# PicoCradle.net
KiCad netlist of a schematic drawn in EAGLE
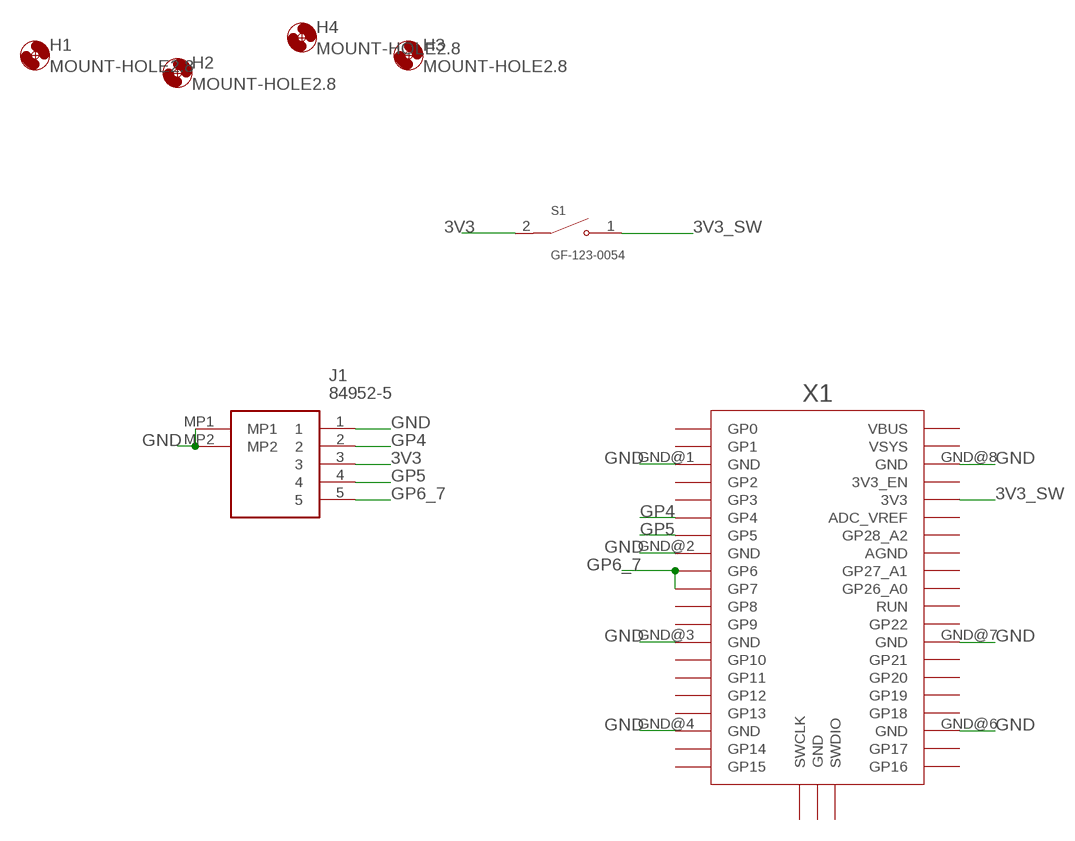
[diagram p0: schematic, sheet 1]

(export (version "E")
  (design (tool "Eeschema 10.0.6"))
  (components
    (comp (ref "H1")
      (value "MOUNT-HOLE2.8")
      (footprint "eagle-import:2,8")
      (libsource (lib "eagle-import") (part "MOUNT-HOLE2.8"))
    )
    (comp (ref "H2")
      (value "MOUNT-HOLE2.8")
      (footprint "eagle-import:2,8")
      (libsource (lib "eagle-import") (part "MOUNT-HOLE2.8"))
    )
    (comp (ref "H3")
      (value "MOUNT-HOLE2.8")
      (footprint "eagle-import:2,8")
      (libsource (lib "eagle-import") (part "MOUNT-HOLE2.8"))
    )
    (comp (ref "H4")
      (value "MOUNT-HOLE2.8")
      (footprint "eagle-import:2,8")
      (libsource (lib "eagle-import") (part "MOUNT-HOLE2.8"))
    )
    (comp (ref "J1")
      (value "84952-5")
      (footprint "eagle-import:849525")
      (libsource (lib "eagle-import") (part "84952-5"))
    )
    (comp (ref "S1")
      (value "GF-123-0054")
      (footprint "eagle-import:SW_GF-123-0054")
      (fields (field (name "MF") "CW Industries"))
      (libsource (lib "eagle-import") (part "GF-123-0054"))
    )
    (comp (ref "X1")
      (value "RPI_PICO_IG-SMD")
      (footprint "eagle-import:RPI_PICO")
      (libsource (lib "eagle-import") (part "RPI_PICO_IG-SMD"))
    )
  )
  (nets
    (net (code "1") (name "/3V3") (class "Default")
      (node (ref "J1") (pin "3") (pinfunction "3_3") (pintype "bidirectional"))
      (node (ref "S1") (pin "2") (pinfunction "2_2") (pintype "passive"))
    )
    (net (code "2") (name "/3V3_SW") (class "Default")
      (node (ref "S1") (pin "1") (pinfunction "1_1") (pintype "passive"))
      (node (ref "X1") (pin "3V3") (pinfunction "3V3_3V3") (pintype "bidirectional"))
    )
    (net (code "3") (name "/GND") (class "Default")
      (node (ref "J1") (pin "1") (pinfunction "1_1") (pintype "bidirectional"))
      (node (ref "J1") (pin "MP1") (pinfunction "MP1_MP1") (pintype "bidirectional"))
      (node (ref "J1") (pin "MP2") (pinfunction "MP2_MP2") (pintype "bidirectional"))
      (node (ref "X1") (pin "GND@1") (pinfunction "GND_GND@1") (pintype "bidirectional"))
      (node (ref "X1") (pin "GND@2") (pinfunction "GND_GND@2") (pintype "bidirectional"))
      (node (ref "X1") (pin "GND@3") (pinfunction "GND_GND@3") (pintype "bidirectional"))
      (node (ref "X1") (pin "GND@4") (pinfunction "GND_GND@4") (pintype "bidirectional"))
      (node (ref "X1") (pin "GND@6") (pinfunction "GND_GND@6") (pintype "bidirectional"))
      (node (ref "X1") (pin "GND@7") (pinfunction "GND_GND@7") (pintype "bidirectional"))
      (node (ref "X1") (pin "GND@8") (pinfunction "GND_GND@8") (pintype "bidirectional"))
    )
    (net (code "4") (name "/GP4") (class "Default")
      (node (ref "J1") (pin "2") (pinfunction "2_2") (pintype "bidirectional"))
      (node (ref "X1") (pin "GP4") (pinfunction "GP4_GP4") (pintype "bidirectional"))
    )
    (net (code "5") (name "/GP5") (class "Default")
      (node (ref "J1") (pin "4") (pinfunction "4_4") (pintype "bidirectional"))
      (node (ref "X1") (pin "GP5") (pinfunction "GP5_GP5") (pintype "bidirectional"))
    )
    (net (code "6") (name "/GP6_7") (class "Default")
      (node (ref "J1") (pin "5") (pinfunction "5_5") (pintype "bidirectional"))
      (node (ref "X1") (pin "GP6") (pinfunction "GP6_GP6") (pintype "bidirectional"))
      (node (ref "X1") (pin "GP7") (pinfunction "GP7_GP7") (pintype "bidirectional"))
    )
    (net (code "7") (name "unconnected-(X1-GND-PadGND@5)") (class "Default")
      (node (ref "X1") (pin "GND@5") (pinfunction "GND_GND@5") (pintype "bidirectional"))
    )
    (net (code "8") (name "unconnected-(X1-Pad3V3_EN)") (class "Default")
      (node (ref "X1") (pin "3V3_EN") (pinfunction "3V3_EN_3V3_EN") (pintype "bidirectional"))
    )
    (net (code "9") (name "unconnected-(X1-PadADC_VREF)") (class "Default")
      (node (ref "X1") (pin "ADC_VREF") (pinfunction "ADC_VREF_ADC_VREF") (pintype "bidirectional"))
    )
    (net (code "10") (name "unconnected-(X1-PadAGND)") (class "Default")
      (node (ref "X1") (pin "AGND") (pinfunction "AGND_AGND") (pintype "bidirectional"))
    )
    (net (code "11") (name "unconnected-(X1-PadGP0)") (class "Default")
      (node (ref "X1") (pin "GP0") (pinfunction "GP0_GP0") (pintype "bidirectional"))
    )
    (net (code "12") (name "unconnected-(X1-PadGP1)") (class "Default")
      (node (ref "X1") (pin "GP1") (pinfunction "GP1_GP1") (pintype "bidirectional"))
    )
    (net (code "13") (name "unconnected-(X1-PadGP2)") (class "Default")
      (node (ref "X1") (pin "GP2") (pinfunction "GP2_GP2") (pintype "bidirectional"))
    )
    (net (code "14") (name "unconnected-(X1-PadGP3)") (class "Default")
      (node (ref "X1") (pin "GP3") (pinfunction "GP3_GP3") (pintype "bidirectional"))
    )
    (net (code "15") (name "unconnected-(X1-PadGP8)") (class "Default")
      (node (ref "X1") (pin "GP8") (pinfunction "GP8_GP8") (pintype "bidirectional"))
    )
    (net (code "16") (name "unconnected-(X1-PadGP9)") (class "Default")
      (node (ref "X1") (pin "GP9") (pinfunction "GP9_GP9") (pintype "bidirectional"))
    )
    (net (code "17") (name "unconnected-(X1-PadGP10)") (class "Default")
      (node (ref "X1") (pin "GP10") (pinfunction "GP10_GP10") (pintype "bidirectional"))
    )
    (net (code "18") (name "unconnected-(X1-PadGP11)") (class "Default")
      (node (ref "X1") (pin "GP11") (pinfunction "GP11_GP11") (pintype "bidirectional"))
    )
    (net (code "19") (name "unconnected-(X1-PadGP12)") (class "Default")
      (node (ref "X1") (pin "GP12") (pinfunction "GP12_GP12") (pintype "bidirectional"))
    )
    (net (code "20") (name "unconnected-(X1-PadGP13)") (class "Default")
      (node (ref "X1") (pin "GP13") (pinfunction "GP13_GP13") (pintype "bidirectional"))
    )
    (net (code "21") (name "unconnected-(X1-PadGP14)") (class "Default")
      (node (ref "X1") (pin "GP14") (pinfunction "GP14_GP14") (pintype "bidirectional"))
    )
    (net (code "22") (name "unconnected-(X1-PadGP15)") (class "Default")
      (node (ref "X1") (pin "GP15") (pinfunction "GP15_GP15") (pintype "bidirectional"))
    )
    (net (code "23") (name "unconnected-(X1-PadGP16)") (class "Default")
      (node (ref "X1") (pin "GP16") (pinfunction "GP16_GP16") (pintype "bidirectional"))
    )
    (net (code "24") (name "unconnected-(X1-PadGP17)") (class "Default")
      (node (ref "X1") (pin "GP17") (pinfunction "GP17_GP17") (pintype "bidirectional"))
    )
    (net (code "25") (name "unconnected-(X1-PadGP18)") (class "Default")
      (node (ref "X1") (pin "GP18") (pinfunction "GP18_GP18") (pintype "bidirectional"))
    )
    (net (code "26") (name "unconnected-(X1-PadGP19)") (class "Default")
      (node (ref "X1") (pin "GP19") (pinfunction "GP19_GP19") (pintype "bidirectional"))
    )
    (net (code "27") (name "unconnected-(X1-PadGP20)") (class "Default")
      (node (ref "X1") (pin "GP20") (pinfunction "GP20_GP20") (pintype "bidirectional"))
    )
    (net (code "28") (name "unconnected-(X1-PadGP21)") (class "Default")
      (node (ref "X1") (pin "GP21") (pinfunction "GP21_GP21") (pintype "bidirectional"))
    )
    (net (code "29") (name "unconnected-(X1-PadGP22)") (class "Default")
      (node (ref "X1") (pin "GP22") (pinfunction "GP22_GP22") (pintype "bidirectional"))
    )
    (net (code "30") (name "unconnected-(X1-PadGP26_A0)") (class "Default")
      (node (ref "X1") (pin "GP26_A0") (pinfunction "GP26_A0_GP26_A0") (pintype "bidirectional"))
    )
    (net (code "31") (name "unconnected-(X1-PadGP27_A1)") (class "Default")
      (node (ref "X1") (pin "GP27_A1") (pinfunction "GP27_A1_GP27_A1") (pintype "bidirectional"))
    )
    (net (code "32") (name "unconnected-(X1-PadGP28_A2)") (class "Default")
      (node (ref "X1") (pin "GP28_A2") (pinfunction "GP28_A2_GP28_A2") (pintype "bidirectional"))
    )
    (net (code "33") (name "unconnected-(X1-PadRUN)") (class "Default")
      (node (ref "X1") (pin "RUN") (pinfunction "RUN_RUN") (pintype "bidirectional"))
    )
    (net (code "34") (name "unconnected-(X1-PadSWCLK)") (class "Default")
      (node (ref "X1") (pin "SWCLK") (pinfunction "SWCLK_SWCLK") (pintype "bidirectional"))
    )
    (net (code "35") (name "unconnected-(X1-PadSWDIO)") (class "Default")
      (node (ref "X1") (pin "SWDIO") (pinfunction "SWDIO_SWDIO") (pintype "bidirectional"))
    )
    (net (code "36") (name "unconnected-(X1-PadVBUS)") (class "Default")
      (node (ref "X1") (pin "VBUS") (pinfunction "VBUS_VBUS") (pintype "bidirectional"))
    )
    (net (code "37") (name "unconnected-(X1-PadVSYS)") (class "Default")
      (node (ref "X1") (pin "VSYS") (pinfunction "VSYS_VSYS") (pintype "bidirectional"))
    )
  )
)
